# Meishino_v10.net
KiCad netlist of a schematic drawn in EAGLE
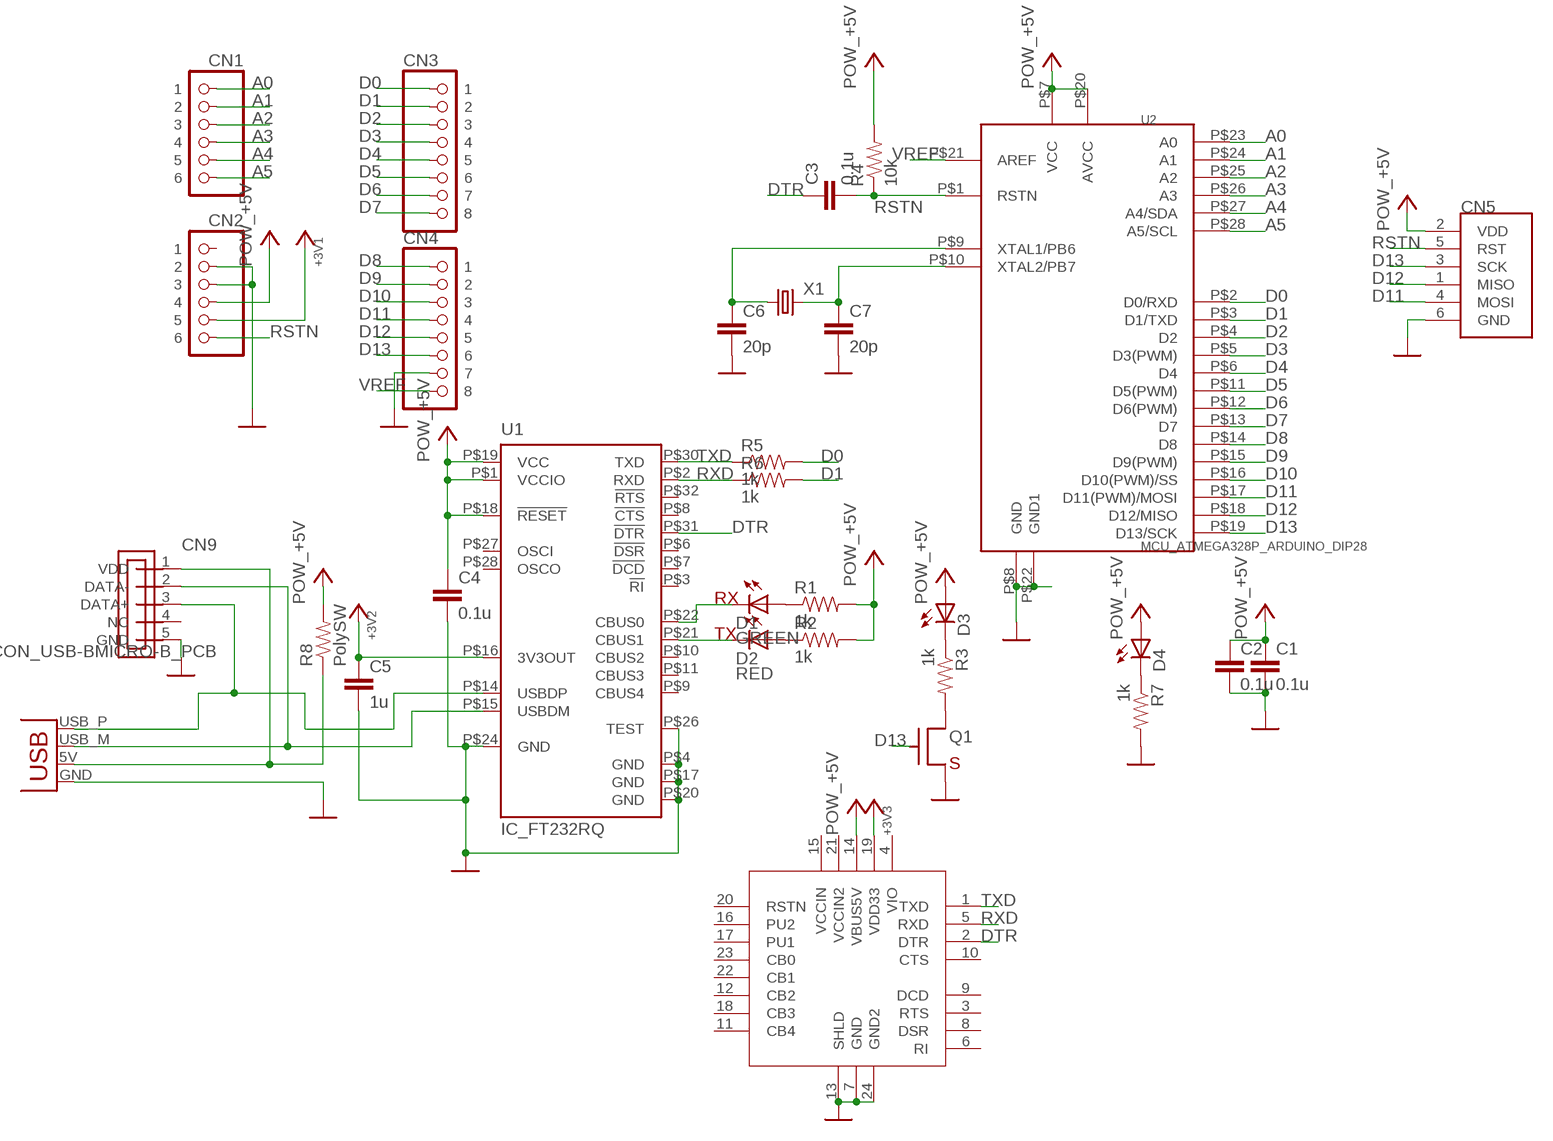
[diagram p0: schematic, sheet 1]

(export (version "E")
  (design (tool "Eeschema 10.0.6"))
  (components
    (comp (ref "C1")
      (value "0.1u")
      (footprint "eagle-import:CAP_TH_5MM_L")
      (libsource (lib "eagle-import") (part "CAPTH_5MML"))
    )
    (comp (ref "C2")
      (value "0.1u")
      (footprint "eagle-import:CAP_TH_5MM_L")
      (libsource (lib "eagle-import") (part "CAPTH_5MML"))
    )
    (comp (ref "C3")
      (value "0.1u")
      (footprint "eagle-import:CAP_TH_5MM_L")
      (libsource (lib "eagle-import") (part "CAPTH_5MML"))
    )
    (comp (ref "C4")
      (value "0.1u")
      (footprint "eagle-import:CAP_TH_5MM_L")
      (libsource (lib "eagle-import") (part "CAPTH_5MML"))
    )
    (comp (ref "C5")
      (value "1u")
      (footprint "eagle-import:CAP_TH_5MM_L")
      (libsource (lib "eagle-import") (part "CAPTH_5MML"))
    )
    (comp (ref "C6")
      (value "20p")
      (footprint "eagle-import:CAP_TH_5MM_L")
      (libsource (lib "eagle-import") (part "CAPTH_5MML"))
    )
    (comp (ref "C7")
      (value "20p")
      (footprint "eagle-import:CAP_TH_5MM_L")
      (libsource (lib "eagle-import") (part "CAPTH_5MML"))
    )
    (comp (ref "CN1")
      (value "CON_PINHD-1X6")
      (footprint "eagle-import:1X06")
      (libsource (lib "eagle-import") (part "CON_PINHD-1X6"))
    )
    (comp (ref "CN2")
      (value "CON_PINHD-1X6")
      (footprint "eagle-import:1X06")
      (libsource (lib "eagle-import") (part "CON_PINHD-1X6"))
    )
    (comp (ref "CN3")
      (value "CON_PINHD-1X8")
      (footprint "eagle-import:1X08")
      (libsource (lib "eagle-import") (part "CON_PINHD-1X8"))
    )
    (comp (ref "CN4")
      (value "CON_PINHD-1X8")
      (footprint "eagle-import:1X08")
      (libsource (lib "eagle-import") (part "CON_PINHD-1X8"))
    )
    (comp (ref "CN5")
      (value "CON_AVRISPTH")
      (footprint "eagle-import:2X03R")
      (libsource (lib "eagle-import") (part "CON_AVRISPTH"))
    )
    (comp (ref "CN9")
      (value "CON_USB-BMICRO-B_PCB")
      (footprint "eagle-import:USB-MICRO-PCB")
      (libsource (lib "eagle-import") (part "CON_USB-BMICRO-B_PCB"))
    )
    (comp (ref "D1")
      (value "GREEN")
      (footprint "eagle-import:SPARKFUN_LED5MM")
      (libsource (lib "eagle-import") (part "LED5MM"))
    )
    (comp (ref "D2")
      (value "RED")
      (footprint "eagle-import:SPARKFUN_LED5MM")
      (libsource (lib "eagle-import") (part "LED5MM"))
    )
    (comp (ref "D3")
      (value "LED5MM")
      (footprint "eagle-import:SPARKFUN_LED5MM")
      (libsource (lib "eagle-import") (part "LED5MM"))
    )
    (comp (ref "D4")
      (value "LED5MM")
      (footprint "eagle-import:SPARKFUN_LED5MM")
      (libsource (lib "eagle-import") (part "LED5MM"))
    )
    (comp (ref "JP2")
      (value "CON_USBPCB")
      (footprint "eagle-import:USB-A-PCB")
      (libsource (lib "eagle-import") (part "CON_USBPCB"))
    )
    (comp (ref "Q1")
      (value "TR_NMOS_2N7000")
      (footprint "eagle-import:TO-92")
      (libsource (lib "eagle-import") (part "TR_NMOS_2N7000"))
    )
    (comp (ref "R1")
      (value "1k")
      (footprint "eagle-import:R_TH_10MM_L")
      (libsource (lib "eagle-import") (part "RESTH_10MML"))
    )
    (comp (ref "R2")
      (value "1k")
      (footprint "eagle-import:R_TH_10MM_L")
      (libsource (lib "eagle-import") (part "RESTH_10MML"))
    )
    (comp (ref "R3")
      (value "1k")
      (footprint "eagle-import:R_TH_10MM_L")
      (libsource (lib "eagle-import") (part "RESTH_10MML"))
    )
    (comp (ref "R4")
      (value "10k")
      (footprint "eagle-import:R_TH_10MM_L")
      (libsource (lib "eagle-import") (part "RESTH_10MML"))
    )
    (comp (ref "R5")
      (value "1k")
      (footprint "eagle-import:R_TH_10MM_L")
      (libsource (lib "eagle-import") (part "RESTH_10MML"))
    )
    (comp (ref "R6")
      (value "1k")
      (footprint "eagle-import:R_TH_10MM_L")
      (libsource (lib "eagle-import") (part "RESTH_10MML"))
    )
    (comp (ref "R7")
      (value "1k")
      (footprint "eagle-import:R_TH_10MM_L")
      (libsource (lib "eagle-import") (part "RESTH_10MML"))
    )
    (comp (ref "R8")
      (value "PolySW")
      (footprint "eagle-import:R_TH_10MM_L")
      (libsource (lib "eagle-import") (part "RESTH_10MML"))
    )
    (comp (ref "U1")
      (value "IC_FT232RQ")
      (footprint "eagle-import:QFN32")
      (libsource (lib "eagle-import") (part "IC_FT232RQ"))
    )
    (comp (ref "U2")
      (value "MCU_ATMEGA328P_ARDUINO_DIP28")
      (footprint "eagle-import:DIP-28P(300MIL)")
      (libsource (lib "eagle-import") (part "MCU_ATMEGA328P_ARDUINO_DIP28"))
    )
    (comp (ref "U3")
      (value "MOD_AE_FT232_DIP24")
      (footprint "eagle-import:DIP24_600MIL")
      (libsource (lib "eagle-import") (part "MOD_AE_FT232_DIP24"))
    )
    (comp (ref "X1")
      (value "XTAL2HC49US")
      (footprint "eagle-import:HC49US")
      (libsource (lib "eagle-import") (part "XTAL2HC49US"))
    )
  )
  (nets
    (net (code "1") (name "/A0") (class "Default")
      (node (ref "CN1") (pin "1") (pinfunction "1_1") (pintype "passive"))
      (node (ref "U2") (pin "P$23") (pinfunction "A0_P$23") (pintype "bidirectional"))
    )
    (net (code "2") (name "/A1") (class "Default")
      (node (ref "CN1") (pin "2") (pinfunction "2_2") (pintype "passive"))
      (node (ref "U2") (pin "P$24") (pinfunction "A1_P$24") (pintype "bidirectional"))
    )
    (net (code "3") (name "/A2") (class "Default")
      (node (ref "CN1") (pin "3") (pinfunction "3_3") (pintype "passive"))
      (node (ref "U2") (pin "P$25") (pinfunction "A2_P$25") (pintype "bidirectional"))
    )
    (net (code "4") (name "/A3") (class "Default")
      (node (ref "CN1") (pin "4") (pinfunction "4_4") (pintype "passive"))
      (node (ref "U2") (pin "P$26") (pinfunction "A3_P$26") (pintype "bidirectional"))
    )
    (net (code "5") (name "/A4") (class "Default")
      (node (ref "CN1") (pin "5") (pinfunction "5_5") (pintype "passive"))
      (node (ref "U2") (pin "P$27") (pinfunction "A4/SDA_P$27") (pintype "bidirectional"))
    )
    (net (code "6") (name "/A5") (class "Default")
      (node (ref "CN1") (pin "6") (pinfunction "6_6") (pintype "passive"))
      (node (ref "U2") (pin "P$28") (pinfunction "A5/SCL_P$28") (pintype "bidirectional"))
    )
    (net (code "7") (name "/D0") (class "Default")
      (node (ref "CN3") (pin "1") (pinfunction "1_1") (pintype "passive"))
      (node (ref "R5") (pin "2") (pinfunction "2_2") (pintype "passive"))
      (node (ref "U2") (pin "P$2") (pinfunction "D0/RXD_P$2") (pintype "bidirectional"))
    )
    (net (code "8") (name "/D1") (class "Default")
      (node (ref "CN3") (pin "2") (pinfunction "2_2") (pintype "passive"))
      (node (ref "R6") (pin "2") (pinfunction "2_2") (pintype "passive"))
      (node (ref "U2") (pin "P$3") (pinfunction "D1/TXD_P$3") (pintype "bidirectional"))
    )
    (net (code "9") (name "/D2") (class "Default")
      (node (ref "CN3") (pin "3") (pinfunction "3_3") (pintype "passive"))
      (node (ref "U2") (pin "P$4") (pinfunction "D2_P$4") (pintype "bidirectional"))
    )
    (net (code "10") (name "/D3") (class "Default")
      (node (ref "CN3") (pin "4") (pinfunction "4_4") (pintype "passive"))
      (node (ref "U2") (pin "P$5") (pinfunction "D3(PWM)_P$5") (pintype "bidirectional"))
    )
    (net (code "11") (name "/D4") (class "Default")
      (node (ref "CN3") (pin "5") (pinfunction "5_5") (pintype "passive"))
      (node (ref "U2") (pin "P$6") (pinfunction "D4_P$6") (pintype "bidirectional"))
    )
    (net (code "12") (name "/D5") (class "Default")
      (node (ref "CN3") (pin "6") (pinfunction "6_6") (pintype "passive"))
      (node (ref "U2") (pin "P$11") (pinfunction "D5(PWM)_P$11") (pintype "bidirectional"))
    )
    (net (code "13") (name "/D6") (class "Default")
      (node (ref "CN3") (pin "7") (pinfunction "7_7") (pintype "passive"))
      (node (ref "U2") (pin "P$12") (pinfunction "D6(PWM)_P$12") (pintype "bidirectional"))
    )
    (net (code "14") (name "/D7") (class "Default")
      (node (ref "CN3") (pin "8") (pinfunction "8_8") (pintype "passive"))
      (node (ref "U2") (pin "P$13") (pinfunction "D7_P$13") (pintype "bidirectional"))
    )
    (net (code "15") (name "/D8") (class "Default")
      (node (ref "CN4") (pin "1") (pinfunction "1_1") (pintype "passive"))
      (node (ref "U2") (pin "P$14") (pinfunction "D8_P$14") (pintype "bidirectional"))
    )
    (net (code "16") (name "/D9") (class "Default")
      (node (ref "CN4") (pin "2") (pinfunction "2_2") (pintype "passive"))
      (node (ref "U2") (pin "P$15") (pinfunction "D9(PWM)_P$15") (pintype "bidirectional"))
    )
    (net (code "17") (name "/D10") (class "Default")
      (node (ref "CN4") (pin "3") (pinfunction "3_3") (pintype "passive"))
      (node (ref "U2") (pin "P$16") (pinfunction "D10(PWM)/SS_P$16") (pintype "bidirectional"))
    )
    (net (code "18") (name "/D11") (class "Default")
      (node (ref "CN4") (pin "4") (pinfunction "4_4") (pintype "passive"))
      (node (ref "CN5") (pin "4") (pinfunction "MOSI_4") (pintype "bidirectional"))
      (node (ref "U2") (pin "P$17") (pinfunction "D11(PWM)/MOSI_P$17") (pintype "bidirectional"))
    )
    (net (code "19") (name "/D12") (class "Default")
      (node (ref "CN4") (pin "5") (pinfunction "5_5") (pintype "passive"))
      (node (ref "CN5") (pin "1") (pinfunction "MISO_1") (pintype "bidirectional"))
      (node (ref "U2") (pin "P$18") (pinfunction "D12/MISO_P$18") (pintype "bidirectional"))
    )
    (net (code "20") (name "/D13") (class "Default")
      (node (ref "CN4") (pin "6") (pinfunction "6_6") (pintype "passive"))
      (node (ref "CN5") (pin "3") (pinfunction "SCK_3") (pintype "bidirectional"))
      (node (ref "Q1") (pin "2") (pinfunction "G_2") (pintype "bidirectional"))
      (node (ref "U2") (pin "P$19") (pinfunction "D13/SCK_P$19") (pintype "bidirectional"))
    )
    (net (code "21") (name "/DTR") (class "Default")
      (node (ref "C3") (pin "1") (pinfunction "1_1") (pintype "passive"))
      (node (ref "U1") (pin "P$31") (pinfunction "~{DTR}_P$31") (pintype "output"))
      (node (ref "U3") (pin "2") (pinfunction "DTR_2") (pintype "bidirectional"))
    )
    (net (code "22") (name "/RSTN") (class "Default")
      (node (ref "C3") (pin "2") (pinfunction "2_2") (pintype "passive"))
      (node (ref "CN2") (pin "6") (pinfunction "6_6") (pintype "passive"))
      (node (ref "CN5") (pin "5") (pinfunction "RST_5") (pintype "bidirectional"))
      (node (ref "R4") (pin "1") (pinfunction "1_1") (pintype "passive"))
      (node (ref "U2") (pin "P$1") (pinfunction "RSTN_P$1") (pintype "bidirectional"))
    )
    (net (code "23") (name "/RXD") (class "Default")
      (node (ref "R6") (pin "1") (pinfunction "1_1") (pintype "passive"))
      (node (ref "U1") (pin "P$2") (pinfunction "RXD_P$2") (pintype "input"))
      (node (ref "U3") (pin "5") (pinfunction "RXD_5") (pintype "bidirectional"))
    )
    (net (code "24") (name "/TXD") (class "Default")
      (node (ref "R5") (pin "1") (pinfunction "1_1") (pintype "passive"))
      (node (ref "U1") (pin "P$30") (pinfunction "TXD_P$30") (pintype "output"))
      (node (ref "U3") (pin "1") (pinfunction "TXD_1") (pintype "bidirectional"))
    )
    (net (code "25") (name "/VREF") (class "Default")
      (node (ref "CN4") (pin "8") (pinfunction "8_8") (pintype "passive"))
      (node (ref "U2") (pin "P$21") (pinfunction "AREF_P$21") (pintype "bidirectional"))
    )
    (net (code "26") (name "Net-(CN9-DATA+)") (class "Default")
      (node (ref "CN9") (pin "3") (pinfunction "DATA+_3") (pintype "bidirectional"))
      (node (ref "JP2") (pin "USB_P") (pinfunction "D+_USB_P") (pintype "bidirectional"))
      (node (ref "U1") (pin "P$14") (pinfunction "USBDP_P$14") (pintype "bidirectional"))
    )
    (net (code "27") (name "Net-(CN9-DATA-)") (class "Default")
      (node (ref "CN9") (pin "2") (pinfunction "DATA-_2") (pintype "bidirectional"))
      (node (ref "JP2") (pin "USB_M") (pinfunction "D-_USB_M") (pintype "bidirectional"))
      (node (ref "U1") (pin "P$15") (pinfunction "USBDM_P$15") (pintype "bidirectional"))
    )
    (net (code "28") (name "Net-(CN9-VDD)") (class "Default")
      (node (ref "CN9") (pin "1") (pinfunction "VDD_1") (pintype "power_in"))
      (node (ref "JP2") (pin "5V") (pinfunction "VBUS_5V") (pintype "bidirectional"))
      (node (ref "R8") (pin "1") (pinfunction "1_1") (pintype "passive"))
    )
    (net (code "29") (name "Net-(D1-C)") (class "Default")
      (node (ref "D1") (pin "K") (pinfunction "C_K") (pintype "passive"))
      (node (ref "U1") (pin "P$22") (pinfunction "CBUS0_P$22") (pintype "bidirectional"))
    )
    (net (code "30") (name "Net-(D1-PadA)") (class "Default")
      (node (ref "D1") (pin "A") (pinfunction "A_A") (pintype "passive"))
      (node (ref "R1") (pin "1") (pinfunction "1_1") (pintype "passive"))
    )
    (net (code "31") (name "Net-(D2-C)") (class "Default")
      (node (ref "D2") (pin "K") (pinfunction "C_K") (pintype "passive"))
      (node (ref "U1") (pin "P$21") (pinfunction "CBUS1_P$21") (pintype "bidirectional"))
    )
    (net (code "32") (name "Net-(D2-PadA)") (class "Default")
      (node (ref "D2") (pin "A") (pinfunction "A_A") (pintype "passive"))
      (node (ref "R2") (pin "1") (pinfunction "1_1") (pintype "passive"))
    )
    (net (code "33") (name "Net-(D3-C)") (class "Default")
      (node (ref "D3") (pin "K") (pinfunction "C_K") (pintype "passive"))
      (node (ref "R3") (pin "1") (pinfunction "1_1") (pintype "passive"))
    )
    (net (code "34") (name "Net-(D4-C)") (class "Default")
      (node (ref "D4") (pin "K") (pinfunction "C_K") (pintype "passive"))
      (node (ref "R7") (pin "1") (pinfunction "1_1") (pintype "passive"))
    )
    (net (code "35") (name "Net-(Q1-D)") (class "Default")
      (node (ref "Q1") (pin "3") (pinfunction "D_3") (pintype "bidirectional"))
      (node (ref "R3") (pin "2") (pinfunction "2_2") (pintype "passive"))
    )
    (net (code "36") (name "Net-(U2-XTAL1{slash}PB6)") (class "Default")
      (node (ref "C6") (pin "1") (pinfunction "1_1") (pintype "passive"))
      (node (ref "U2") (pin "P$9") (pinfunction "XTAL1/PB6_P$9") (pintype "bidirectional"))
      (node (ref "X1") (pin "1") (pinfunction "1_1") (pintype "passive"))
    )
    (net (code "37") (name "Net-(U2-XTAL2{slash}PB7)") (class "Default")
      (node (ref "C7") (pin "1") (pinfunction "1_1") (pintype "passive"))
      (node (ref "U2") (pin "P$10") (pinfunction "XTAL2/PB7_P$10") (pintype "bidirectional"))
      (node (ref "X1") (pin "2") (pinfunction "2_2") (pintype "passive"))
    )
    (net (code "38") (name "POW_+3V3") (class "Default")
      (node (ref "C5") (pin "1") (pinfunction "1_1") (pintype "passive"))
      (node (ref "CN2") (pin "5") (pinfunction "5_5") (pintype "passive"))
      (node (ref "U1") (pin "P$16") (pinfunction "3V3OUT_P$16") (pintype "output"))
      (node (ref "U3") (pin "19") (pinfunction "VDD33_19") (pintype "bidirectional"))
    )
    (net (code "39") (name "POW_+5V") (class "Default")
      (node (ref "C1") (pin "1") (pinfunction "1_1") (pintype "passive"))
      (node (ref "C2") (pin "1") (pinfunction "1_1") (pintype "passive"))
      (node (ref "C4") (pin "1") (pinfunction "1_1") (pintype "passive"))
      (node (ref "CN2") (pin "4") (pinfunction "4_4") (pintype "passive"))
      (node (ref "CN5") (pin "2") (pinfunction "VDD_2") (pintype "bidirectional"))
      (node (ref "D3") (pin "A") (pinfunction "A_A") (pintype "passive"))
      (node (ref "D4") (pin "A") (pinfunction "A_A") (pintype "passive"))
      (node (ref "R1") (pin "2") (pinfunction "2_2") (pintype "passive"))
      (node (ref "R2") (pin "2") (pinfunction "2_2") (pintype "passive"))
      (node (ref "R4") (pin "2") (pinfunction "2_2") (pintype "passive"))
      (node (ref "R8") (pin "2") (pinfunction "2_2") (pintype "passive"))
      (node (ref "U1") (pin "P$1") (pinfunction "VCCIO_P$1") (pintype "power_in"))
      (node (ref "U1") (pin "P$18") (pinfunction "~{RESET}_P$18") (pintype "input"))
      (node (ref "U1") (pin "P$19") (pinfunction "VCC_P$19") (pintype "power_in"))
      (node (ref "U2") (pin "P$20") (pinfunction "AVCC_P$20") (pintype "power_in"))
      (node (ref "U2") (pin "P$7") (pinfunction "VCC_P$7") (pintype "power_in"))
      (node (ref "U3") (pin "14") (pinfunction "VBUS5V_14") (pintype "bidirectional"))
    )
    (net (code "40") (name "POW_GND") (class "Default")
      (node (ref "C1") (pin "2") (pinfunction "2_2") (pintype "passive"))
      (node (ref "C2") (pin "2") (pinfunction "2_2") (pintype "passive"))
      (node (ref "C4") (pin "2") (pinfunction "2_2") (pintype "passive"))
      (node (ref "C5") (pin "2") (pinfunction "2_2") (pintype "passive"))
      (node (ref "C6") (pin "2") (pinfunction "2_2") (pintype "passive"))
      (node (ref "C7") (pin "2") (pinfunction "2_2") (pintype "passive"))
      (node (ref "CN2") (pin "2") (pinfunction "2_2") (pintype "passive"))
      (node (ref "CN2") (pin "3") (pinfunction "3_3") (pintype "passive"))
      (node (ref "CN4") (pin "7") (pinfunction "7_7") (pintype "passive"))
      (node (ref "CN5") (pin "6") (pinfunction "GND_6") (pintype "bidirectional"))
      (node (ref "CN9") (pin "5") (pinfunction "GND_5") (pintype "power_in"))
      (node (ref "JP2") (pin "GND") (pinfunction "GND_GND") (pintype "bidirectional"))
      (node (ref "Q1") (pin "1") (pinfunction "S_1") (pintype "bidirectional"))
      (node (ref "R7") (pin "2") (pinfunction "2_2") (pintype "passive"))
      (node (ref "U1") (pin "P$17") (pinfunction "GND_P$17") (pintype "power_in"))
      (node (ref "U1") (pin "P$20") (pinfunction "GND_P$20") (pintype "power_in"))
      (node (ref "U1") (pin "P$24") (pinfunction "GND_P$24") (pintype "power_in"))
      (node (ref "U1") (pin "P$26") (pinfunction "TEST_P$26") (pintype "input"))
      (node (ref "U1") (pin "P$4") (pinfunction "GND_P$4") (pintype "power_in"))
      (node (ref "U2") (pin "P$22") (pinfunction "GND1_P$22") (pintype "power_in"))
      (node (ref "U2") (pin "P$8") (pinfunction "GND_P$8") (pintype "power_in"))
      (node (ref "U3") (pin "13") (pinfunction "SHLD_13") (pintype "bidirectional"))
      (node (ref "U3") (pin "24") (pinfunction "GND2_24") (pintype "bidirectional"))
      (node (ref "U3") (pin "7") (pinfunction "GND_7") (pintype "bidirectional"))
    )
    (net (code "41") (name "unconnected-(CN2-Pad1)") (class "Default")
      (node (ref "CN2") (pin "1") (pinfunction "1_1") (pintype "passive"))
    )
    (net (code "42") (name "unconnected-(CN9-NC-Pad4)") (class "Default")
      (node (ref "CN9") (pin "4") (pinfunction "NC_4") (pintype "bidirectional"))
    )
    (net (code "43") (name "unconnected-(U1-CBUS2-PadP$10)") (class "Default")
      (node (ref "U1") (pin "P$10") (pinfunction "CBUS2_P$10") (pintype "bidirectional"))
    )
    (net (code "44") (name "unconnected-(U1-CBUS3-PadP$11)") (class "Default")
      (node (ref "U1") (pin "P$11") (pinfunction "CBUS3_P$11") (pintype "bidirectional"))
    )
    (net (code "45") (name "unconnected-(U1-CBUS4-PadP$9)") (class "Default")
      (node (ref "U1") (pin "P$9") (pinfunction "CBUS4_P$9") (pintype "bidirectional"))
    )
    (net (code "46") (name "unconnected-(U1-OSCI-PadP$27)") (class "Default")
      (node (ref "U1") (pin "P$27") (pinfunction "OSCI_P$27") (pintype "input"))
    )
    (net (code "47") (name "unconnected-(U1-OSCO-PadP$28)") (class "Default")
      (node (ref "U1") (pin "P$28") (pinfunction "OSCO_P$28") (pintype "output"))
    )
    (net (code "48") (name "unconnected-(U1-~{CTS}-PadP$8)") (class "Default")
      (node (ref "U1") (pin "P$8") (pinfunction "~{CTS}_P$8") (pintype "input"))
    )
    (net (code "49") (name "unconnected-(U1-~{DCD}-PadP$7)") (class "Default")
      (node (ref "U1") (pin "P$7") (pinfunction "~{DCD}_P$7") (pintype "input"))
    )
    (net (code "50") (name "unconnected-(U1-~{DSR}-PadP$6)") (class "Default")
      (node (ref "U1") (pin "P$6") (pinfunction "~{DSR}_P$6") (pintype "input"))
    )
    (net (code "51") (name "unconnected-(U1-~{RI}-PadP$3)") (class "Default")
      (node (ref "U1") (pin "P$3") (pinfunction "~{RI}_P$3") (pintype "input"))
    )
    (net (code "52") (name "unconnected-(U1-~{RTS}-PadP$32)") (class "Default")
      (node (ref "U1") (pin "P$32") (pinfunction "~{RTS}_P$32") (pintype "output"))
    )
    (net (code "53") (name "unconnected-(U3-CB0-Pad23)") (class "Default")
      (node (ref "U3") (pin "23") (pinfunction "CB0_23") (pintype "bidirectional"))
    )
    (net (code "54") (name "unconnected-(U3-CB1-Pad22)") (class "Default")
      (node (ref "U3") (pin "22") (pinfunction "CB1_22") (pintype "bidirectional"))
    )
    (net (code "55") (name "unconnected-(U3-CB2-Pad12)") (class "Default")
      (node (ref "U3") (pin "12") (pinfunction "CB2_12") (pintype "bidirectional"))
    )
    (net (code "56") (name "unconnected-(U3-CB3-Pad18)") (class "Default")
      (node (ref "U3") (pin "18") (pinfunction "CB3_18") (pintype "bidirectional"))
    )
    (net (code "57") (name "unconnected-(U3-CB4-Pad11)") (class "Default")
      (node (ref "U3") (pin "11") (pinfunction "CB4_11") (pintype "bidirectional"))
    )
    (net (code "58") (name "unconnected-(U3-CTS-Pad10)") (class "Default")
      (node (ref "U3") (pin "10") (pinfunction "CTS_10") (pintype "bidirectional"))
    )
    (net (code "59") (name "unconnected-(U3-DCD-Pad9)") (class "Default")
      (node (ref "U3") (pin "9") (pinfunction "DCD_9") (pintype "bidirectional"))
    )
    (net (code "60") (name "unconnected-(U3-DSR-Pad8)") (class "Default")
      (node (ref "U3") (pin "8") (pinfunction "DSR_8") (pintype "bidirectional"))
    )
    (net (code "61") (name "unconnected-(U3-PU1-Pad17)") (class "Default")
      (node (ref "U3") (pin "17") (pinfunction "PU1_17") (pintype "bidirectional"))
    )
    (net (code "62") (name "unconnected-(U3-PU2-Pad16)") (class "Default")
      (node (ref "U3") (pin "16") (pinfunction "PU2_16") (pintype "bidirectional"))
    )
    (net (code "63") (name "unconnected-(U3-RI-Pad6)") (class "Default")
      (node (ref "U3") (pin "6") (pinfunction "RI_6") (pintype "bidirectional"))
    )
    (net (code "64") (name "unconnected-(U3-RSTN-Pad20)") (class "Default")
      (node (ref "U3") (pin "20") (pinfunction "RSTN_20") (pintype "bidirectional"))
    )
    (net (code "65") (name "unconnected-(U3-RTS-Pad3)") (class "Default")
      (node (ref "U3") (pin "3") (pinfunction "RTS_3") (pintype "bidirectional"))
    )
    (net (code "66") (name "unconnected-(U3-VCCIN-Pad15)") (class "Default")
      (node (ref "U3") (pin "15") (pinfunction "VCCIN_15") (pintype "bidirectional"))
    )
    (net (code "67") (name "unconnected-(U3-VCCIN2-Pad21)") (class "Default")
      (node (ref "U3") (pin "21") (pinfunction "VCCIN2_21") (pintype "bidirectional"))
    )
    (net (code "68") (name "unconnected-(U3-VIO-Pad4)") (class "Default")
      (node (ref "U3") (pin "4") (pinfunction "VIO_4") (pintype "bidirectional"))
    )
  )
)
